# schematics_easyEDA_rev0_4.net
KiCad netlist of a schematic drawn in EasyEDA
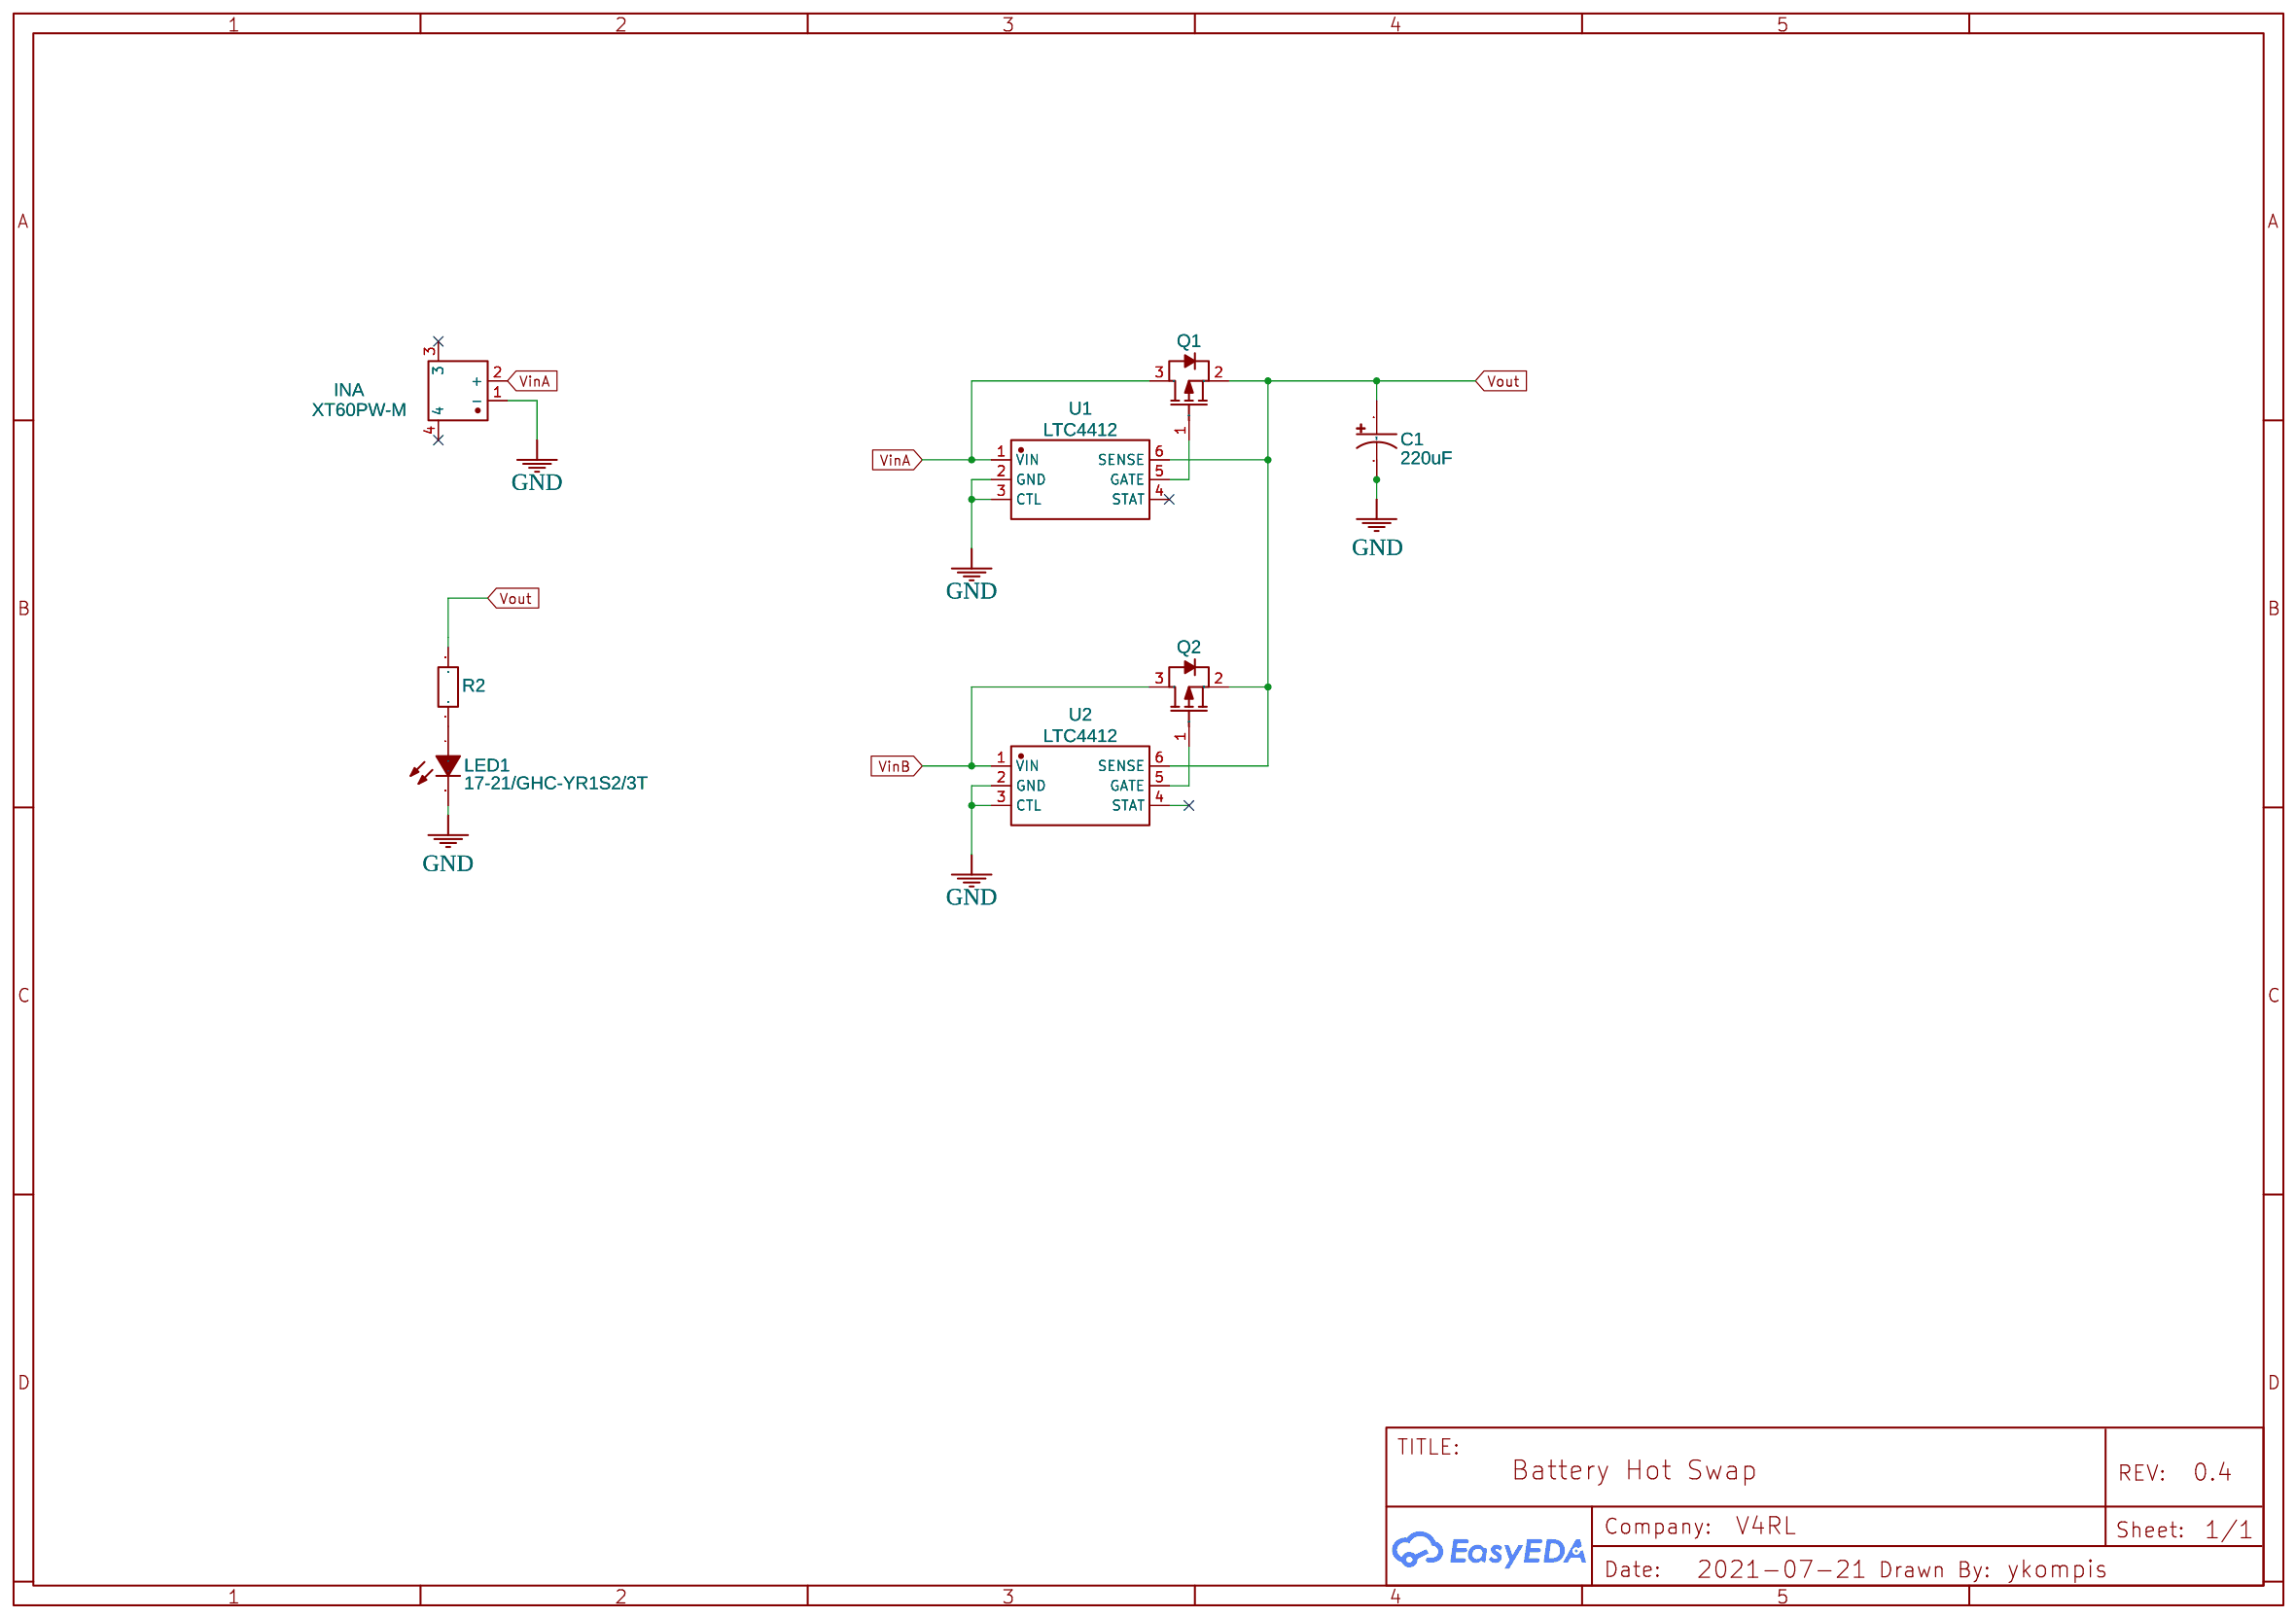
[diagram p0: Battery Hot Swap rev0.4]
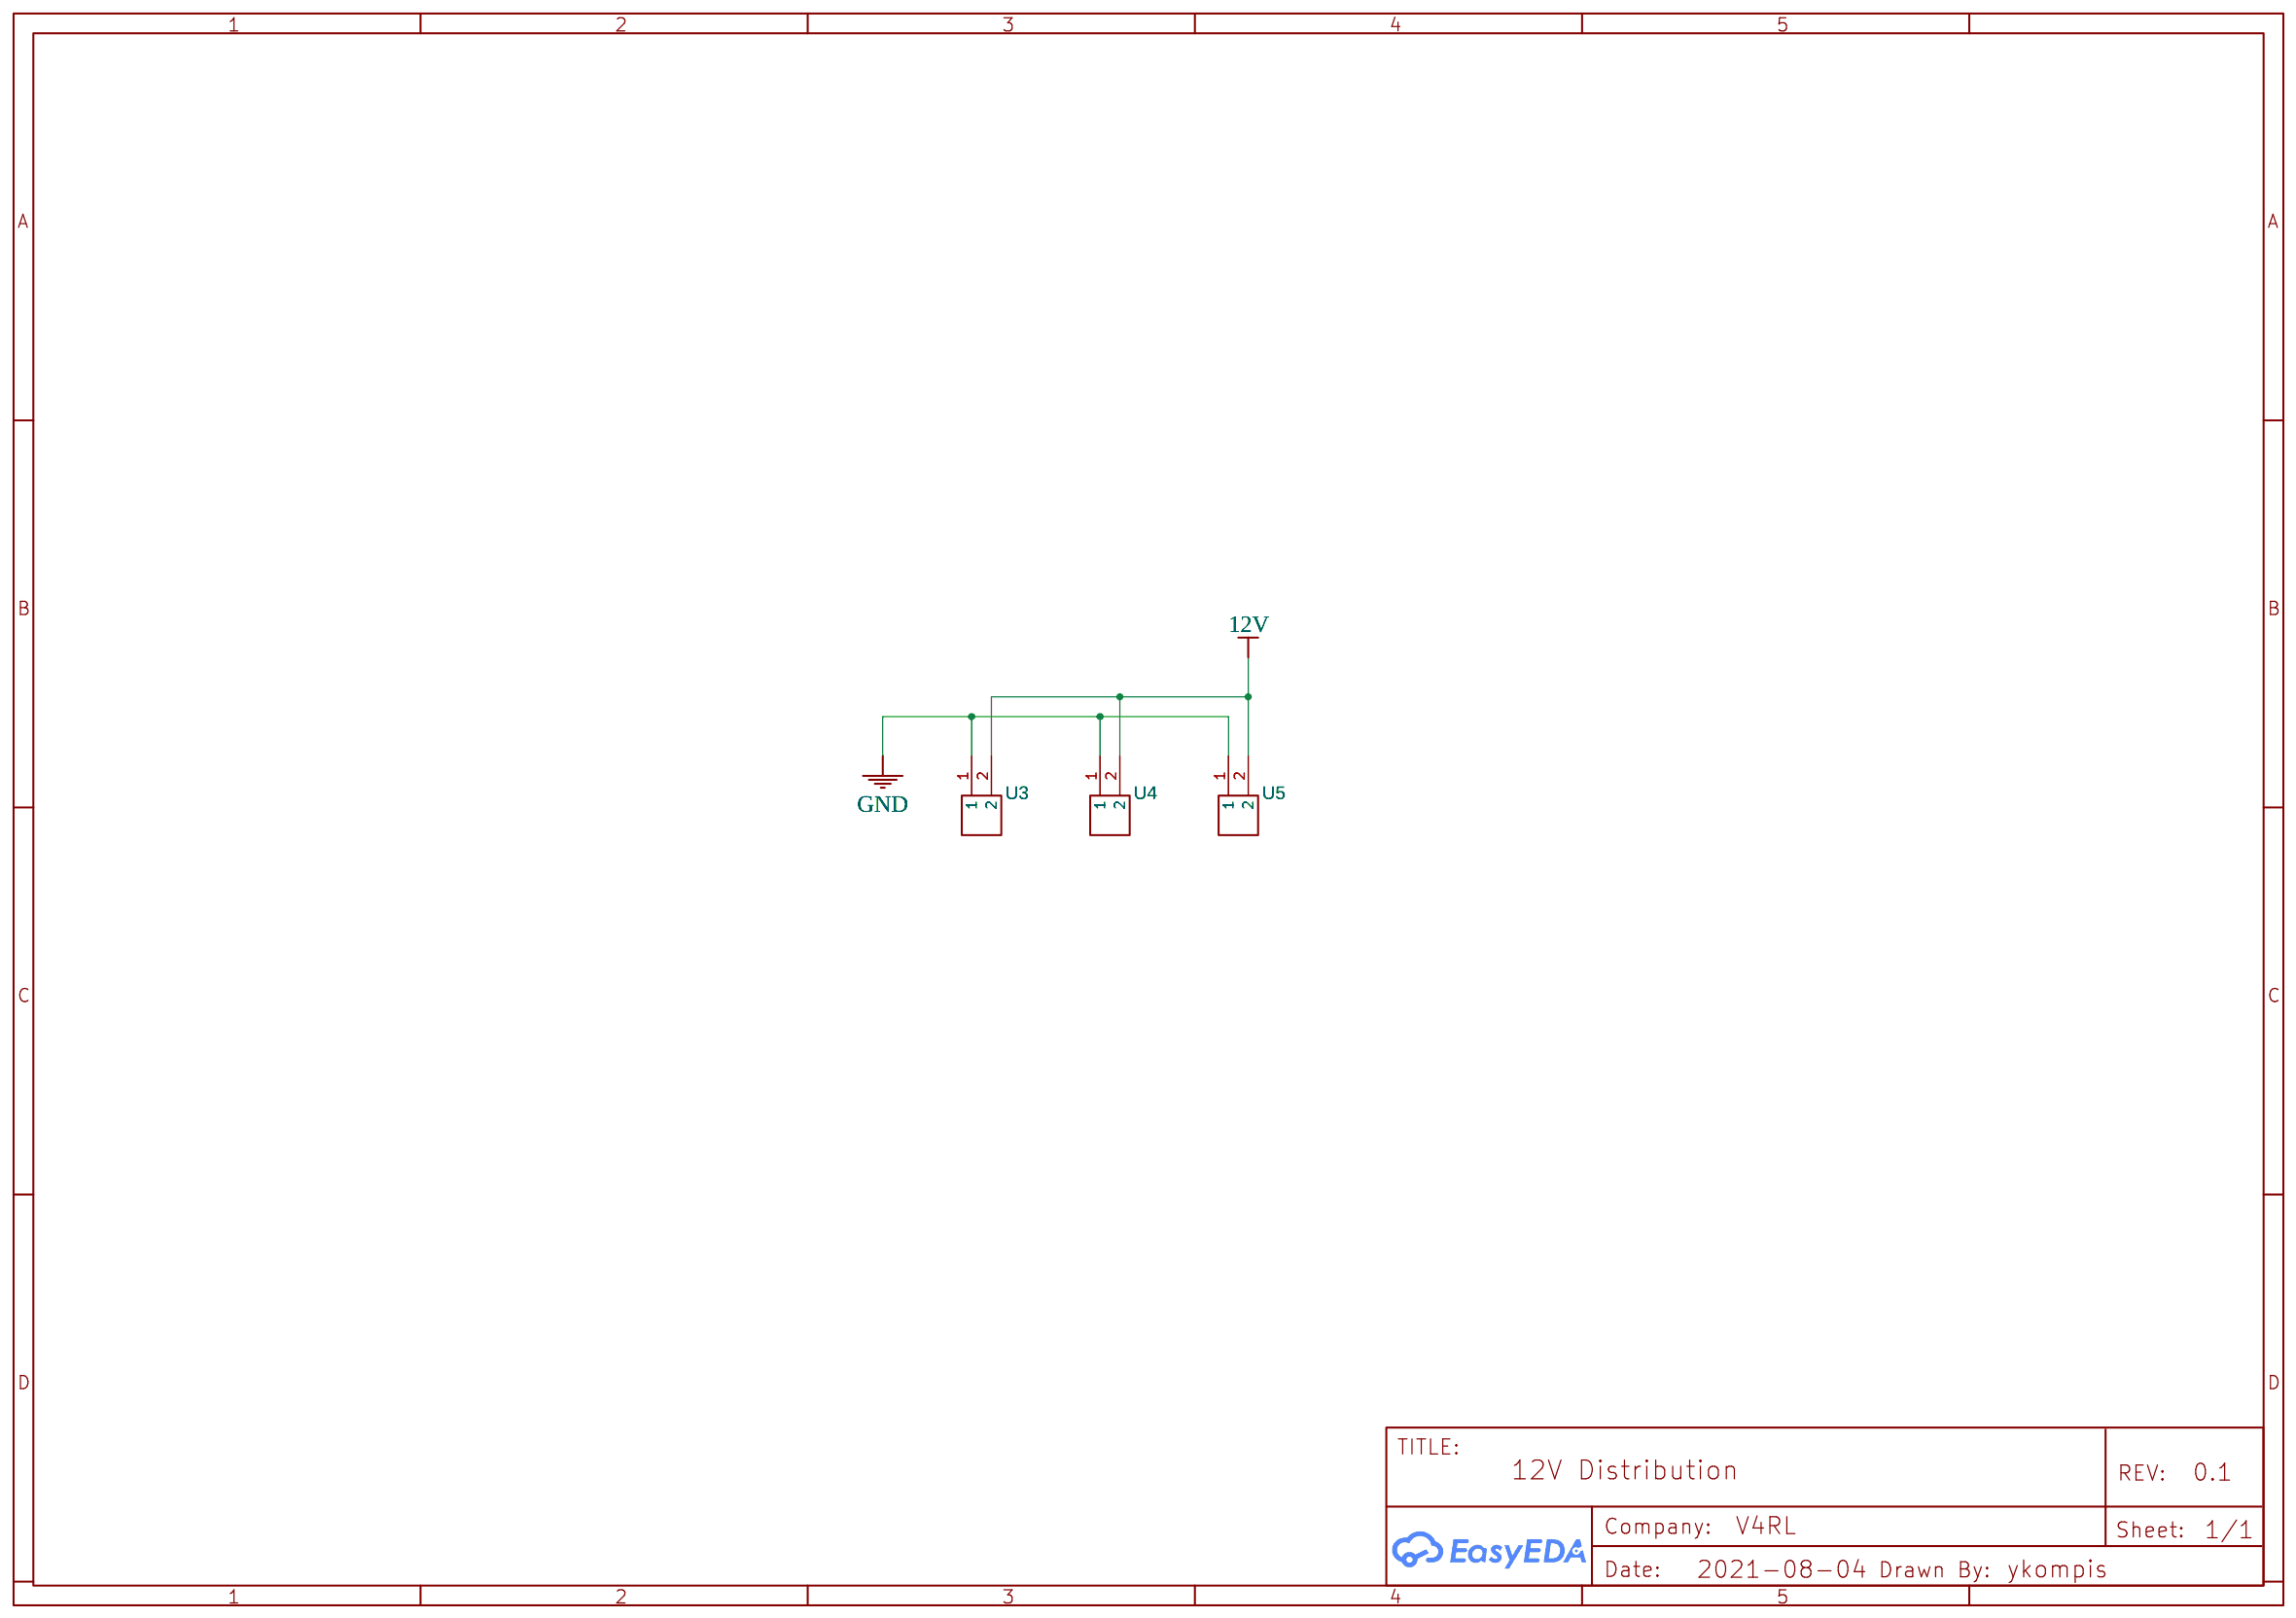
[diagram p1: 12V Distribution rev0.1]

(export (version "E")
  (design (tool "Eeschema 10.0.6"))
  (components
    (comp (ref "C1")
      (value "220uF")
      (fields
        (field (name "BOM_Manufacturer Part") "EEEFC1V221AP")
        (field (name "BOM_Supplier Part") "C401627")
      )
      (libsource (lib "") (part "EEEFC1V221AP"))
    )
    (comp (ref "INA")
      (value "XT60PW-M")
      (fields (field (name "BOM_Supplier Part") "C98732"))
      (libsource (lib "") (part "XT60PW-M"))
    )
    (comp (ref "LED1")
      (value "17-21/GHC-YR1S2/3T")
      (fields (field (name "BOM_Supplier Part") "C73546"))
      (libsource (lib "") (part "17-21/GHC-YR1S2/3T"))
    )
    (comp (ref "Q1")
      (value "FDD4685")
      (fields (field (name "BOM_Supplier Part") "C258227"))
      (libsource (lib "") (part "FDD4685"))
    )
    (comp (ref "Q2")
      (value "FDD4685")
      (fields (field (name "BOM_Supplier Part") "C258227"))
      (libsource (lib "") (part "FDD4685"))
    )
    (comp (ref "R2")
      (value "ARG05DTC1000")
      (fields (field (name "BOM_Supplier Part") "C1509658"))
      (libsource (lib "") (part "ARG05DTC1000"))
    )
    (comp (ref "U1")
      (value "LTC4412")
      (fields
        (field (name "BOM_Manufacturer Part") "LTC4412ES6#TRPBF")
        (field (name "BOM_Supplier Part") "C514442")
      )
      (libsource (lib "") (part "LTC4412ES6#TRPBF"))
    )
    (comp (ref "U2")
      (value "LTC4412")
      (fields
        (field (name "BOM_Manufacturer Part") "LTC4412ES6#TRPBF")
        (field (name "BOM_Supplier Part") "C514442")
      )
      (libsource (lib "") (part "LTC4412ES6#TRPBF"))
    )
    (comp (ref "U3") (value "MOLEX 430450200") (libsource (lib "") (part "MOLEX 430450200")))
    (comp (ref "U4") (value "MOLEX 430450200") (libsource (lib "") (part "MOLEX 430450200")))
    (comp (ref "U5") (value "MOLEX 430450200") (libsource (lib "") (part "MOLEX 430450200")))
  )
  (nets
    (net (code "1") (name "12V") (class "Default")
      (node (ref "U3") (pin "2") (pinfunction "2_2") (pintype "unspecified"))
      (node (ref "U4") (pin "2") (pinfunction "2_2") (pintype "unspecified"))
      (node (ref "U5") (pin "2") (pinfunction "2_2") (pintype "unspecified"))
    )
    (net (code "2") (name "GND") (class "Default")
      (node (ref "C1") (pin "2") (pinfunction "2_2") (pintype "unspecified"))
      (node (ref "INA") (pin "1") (pinfunction "-_1") (pintype "unspecified"))
      (node (ref "LED1") (pin "2") (pinfunction "-_2") (pintype "input"))
      (node (ref "U1") (pin "2") (pinfunction "GND_2") (pintype "unspecified"))
      (node (ref "U1") (pin "3") (pinfunction "CTL_3") (pintype "unspecified"))
      (node (ref "U2") (pin "2") (pinfunction "GND_2") (pintype "unspecified"))
      (node (ref "U2") (pin "3") (pinfunction "CTL_3") (pintype "unspecified"))
      (node (ref "U3") (pin "1") (pinfunction "1_1") (pintype "unspecified"))
      (node (ref "U4") (pin "1") (pinfunction "1_1") (pintype "unspecified"))
      (node (ref "U5") (pin "1") (pinfunction "1_1") (pintype "unspecified"))
    )
    (net (code "3") (name "Net-(LED1-+)") (class "Default")
      (node (ref "LED1") (pin "1") (pinfunction "+_1") (pintype "input"))
      (node (ref "R2") (pin "1") (pinfunction "1_1") (pintype "unspecified"))
    )
    (net (code "4") (name "Net-(Q1-G)") (class "Default")
      (node (ref "Q1") (pin "1") (pinfunction "G_1") (pintype "unspecified"))
      (node (ref "U1") (pin "5") (pinfunction "GATE_5") (pintype "unspecified"))
    )
    (net (code "5") (name "Net-(Q2-G)") (class "Default")
      (node (ref "Q2") (pin "1") (pinfunction "G_1") (pintype "unspecified"))
      (node (ref "U2") (pin "5") (pinfunction "GATE_5") (pintype "unspecified"))
    )
    (net (code "6") (name "VinA") (class "Default")
      (node (ref "INA") (pin "2") (pinfunction "+_2") (pintype "unspecified"))
      (node (ref "Q1") (pin "3") (pinfunction "D_3") (pintype "unspecified"))
      (node (ref "U1") (pin "1") (pinfunction "VIN_1") (pintype "unspecified"))
    )
    (net (code "7") (name "VinB") (class "Default")
      (node (ref "Q2") (pin "3") (pinfunction "D_3") (pintype "unspecified"))
      (node (ref "U2") (pin "1") (pinfunction "VIN_1") (pintype "unspecified"))
    )
    (net (code "8") (name "Vout") (class "Default")
      (node (ref "C1") (pin "1") (pinfunction "1_1") (pintype "unspecified"))
      (node (ref "Q1") (pin "2") (pinfunction "S_2") (pintype "unspecified"))
      (node (ref "Q2") (pin "2") (pinfunction "S_2") (pintype "unspecified"))
      (node (ref "R2") (pin "2") (pinfunction "2_2") (pintype "unspecified"))
      (node (ref "U1") (pin "6") (pinfunction "SENSE_6") (pintype "unspecified"))
      (node (ref "U2") (pin "6") (pinfunction "SENSE_6") (pintype "unspecified"))
    )
    (net (code "9") (name "unconnected-(INA-Pad3)") (class "Default")
      (node (ref "INA") (pin "3") (pinfunction "3_3") (pintype "unspecified+no_connect"))
    )
    (net (code "10") (name "unconnected-(INA-Pad4)") (class "Default")
      (node (ref "INA") (pin "4") (pinfunction "4_4") (pintype "unspecified+no_connect"))
    )
    (net (code "11") (name "unconnected-(U1-STAT-Pad4)") (class "Default")
      (node (ref "U1") (pin "4") (pinfunction "STAT_4") (pintype "unspecified+no_connect"))
    )
    (net (code "12") (name "unconnected-(U2-STAT-Pad4)") (class "Default")
      (node (ref "U2") (pin "4") (pinfunction "STAT_4") (pintype "unspecified+no_connect"))
    )
  )
)
